# ProxSensPCB.net
KiCad netlist of a schematic drawn in Altium Designer
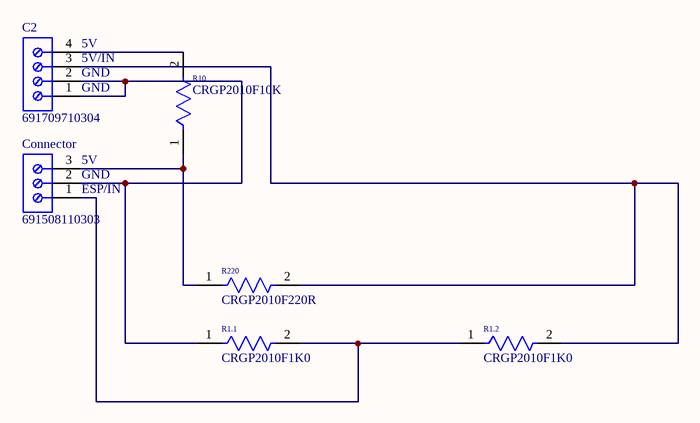
[diagram p0: ProxSensPCB.SchDoc]

(export (version "E")
  (design (tool "Eeschema 10.0.6"))
  (components
    (comp (ref "C2")
      (value "691709710304")
      (footprint "691709710304")
      (fields (field (name "VOLTAGE") "300V"))
      (libsource (lib "Altium Content Vault") (part "TBL - 1R - 04P - Screw"))
    )
    (comp (ref "Connector")
      (value "691508110303")
      (footprint "691508110303")
      (fields (field (name "VOLTAGE") "300V"))
      (libsource (lib "Altium Content Vault") (part "TBL - 1R - 03P - Screw"))
    )
    (comp (ref "R1.1")
      (value "CRGP2010F1K0")
      (footprint "FP-CRGP2010-IPC_C")
      (description "CRGP2010 1KΩ 1.25W ±100ppm/°C 1% 400V")
      (fields
        (field (name "OCTOPART") "https://octopart.com/crgp2010f1k0-te+connectivity-91018979")
        (field (name "TOLERANCE") "0.01")
      )
      (libsource (lib "Altium Content Vault") (part "1029c3af85768c4190bb7ad29bc67b5"))
    )
    (comp (ref "R1.2")
      (value "CRGP2010F1K0")
      (footprint "FP-CRGP2010-IPC_C")
      (description "CRGP2010 1KΩ 1.25W ±100ppm/°C 1% 400V")
      (fields
        (field (name "OCTOPART") "https://octopart.com/crgp2010f1k0-te+connectivity-91018979")
        (field (name "TOLERANCE") "0.01")
      )
      (libsource (lib "Altium Content Vault") (part "1029c3af85768c4190bb7ad29bc67b5"))
    )
    (comp (ref "R10")
      (value "CRGP2010F10K")
      (footprint "FP-CRGP2010-IPC_C")
      (description "CRGP2010 10KΩ 1.25W ±100ppm/°C 1% 400V")
      (fields
        (field (name "OCTOPART") "https://octopart.com/crgp2010f10k-te+connectivity-91018965")
        (field (name "MANUFACTURER") "TE")
      )
      (libsource (lib "Altium Content Vault") (part "1029c3af85768c4190bb7ad29bc67b5"))
    )
    (comp (ref "R220")
      (value "CRGP2010F220R")
      (footprint "FP-CRGP2010-IPC_C")
      (description "CRGP2010 220Ω 1.25W ±100ppm/°C 1% 400V")
      (fields
        (field (name "TOLERANCE") "0.01")
        (field (name "OCTOPART") "https://octopart.com/crgp2010f220r-te+connectivity-91018985")
      )
      (libsource (lib "Altium Content Vault") (part "1029c3af85768c4190bb7ad29bc67b5"))
    )
  )
  (nets
    (net (code "1") (name "Net-(C2-Pad1)") (class "Default")
      (node (ref "C2") (pin "1") (pinfunction "1_1") (pintype "passive"))
      (node (ref "C2") (pin "2") (pinfunction "2_2") (pintype "passive"))
      (node (ref "Connector") (pin "2") (pinfunction "2_2") (pintype "passive"))
      (node (ref "R1.1") (pin "1") (pinfunction "1_1") (pintype "passive"))
    )
    (net (code "2") (name "Net-(C2-Pad3)") (class "Default")
      (node (ref "C2") (pin "3") (pinfunction "3_3") (pintype "passive"))
      (node (ref "R1.2") (pin "2") (pinfunction "2_2") (pintype "passive"))
      (node (ref "R220") (pin "2") (pinfunction "2_2") (pintype "passive"))
    )
    (net (code "3") (name "Net-(C2-Pad4)") (class "Default")
      (node (ref "C2") (pin "4") (pinfunction "4_4") (pintype "passive"))
      (node (ref "R10") (pin "2") (pinfunction "2_2") (pintype "passive"))
    )
    (net (code "4") (name "Net-(Connector-Pad1)") (class "Default")
      (node (ref "Connector") (pin "1") (pinfunction "1_1") (pintype "passive"))
      (node (ref "R1.1") (pin "2") (pinfunction "2_2") (pintype "passive"))
      (node (ref "R1.2") (pin "1") (pinfunction "1_1") (pintype "passive"))
    )
    (net (code "5") (name "Net-(Connector-Pad3)") (class "Default")
      (node (ref "Connector") (pin "3") (pinfunction "3_3") (pintype "passive"))
      (node (ref "R10") (pin "1") (pinfunction "1_1") (pintype "passive"))
      (node (ref "R220") (pin "1") (pinfunction "1_1") (pintype "passive"))
    )
  )
)
